# NEW_POT.net
KiCad netlist of a schematic drawn in EAGLE
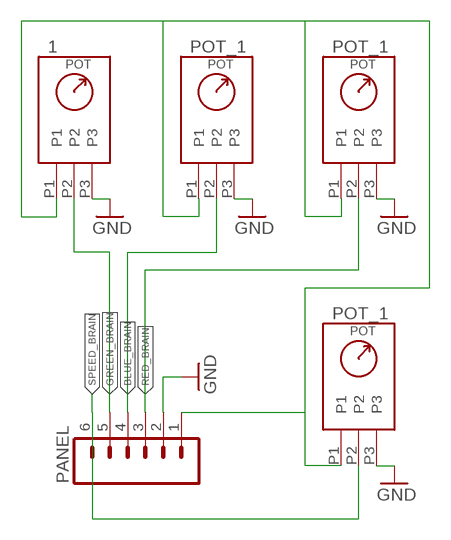
[diagram p0: schematic, sheet 1]

(export (version "E")
  (design (tool "Eeschema 10.0.6"))
  (components
    (comp (ref "DAS")
      (value "1")
      (footprint "eagle-import:POT_1")
      (libsource (lib "eagle-import") (part "POT_1"))
    )
    (comp (ref "PANEL")
      (value "M06NO_SILK_FEMALE_PTH")
      (footprint "eagle-import:1X06_NO_SILK")
      (libsource (lib "eagle-import") (part "M06NO_SILK_FEMALE_PTH"))
    )
    (comp (ref "U$2")
      (value "POT_1")
      (footprint "eagle-import:POT_1")
      (libsource (lib "eagle-import") (part "POT_1"))
    )
    (comp (ref "U$3")
      (value "POT_1")
      (footprint "eagle-import:POT_1")
      (libsource (lib "eagle-import") (part "POT_1"))
    )
    (comp (ref "U$4")
      (value "POT_1")
      (footprint "eagle-import:POT_1")
      (libsource (lib "eagle-import") (part "POT_1"))
    )
  )
  (nets
    (net (code "1") (name "BLUE_BRAIN") (class "Default")
      (node (ref "PANEL") (pin "4") (pinfunction "4_4") (pintype "passive"))
      (node (ref "U$2") (pin "P2") (pinfunction "P2_P2") (pintype "bidirectional"))
    )
    (net (code "2") (name "GND") (class "Default")
      (node (ref "DAS") (pin "P3") (pinfunction "P3_P3") (pintype "bidirectional"))
      (node (ref "PANEL") (pin "2") (pinfunction "2_2") (pintype "passive"))
      (node (ref "U$2") (pin "P3") (pinfunction "P3_P3") (pintype "bidirectional"))
      (node (ref "U$3") (pin "P3") (pinfunction "P3_P3") (pintype "bidirectional"))
      (node (ref "U$4") (pin "P3") (pinfunction "P3_P3") (pintype "bidirectional"))
    )
    (net (code "3") (name "GREEN_BRAIN") (class "Default")
      (node (ref "DAS") (pin "P2") (pinfunction "P2_P2") (pintype "bidirectional"))
      (node (ref "PANEL") (pin "5") (pinfunction "5_5") (pintype "passive"))
    )
    (net (code "4") (name "Net-(DAS-PadP1)") (class "Default")
      (node (ref "DAS") (pin "P1") (pinfunction "P1_P1") (pintype "bidirectional"))
      (node (ref "PANEL") (pin "1") (pinfunction "1_1") (pintype "passive"))
      (node (ref "U$2") (pin "P1") (pinfunction "P1_P1") (pintype "bidirectional"))
      (node (ref "U$3") (pin "P1") (pinfunction "P1_P1") (pintype "bidirectional"))
      (node (ref "U$4") (pin "P1") (pinfunction "P1_P1") (pintype "bidirectional"))
    )
    (net (code "5") (name "RED_BRAIN") (class "Default")
      (node (ref "PANEL") (pin "3") (pinfunction "3_3") (pintype "passive"))
      (node (ref "U$3") (pin "P2") (pinfunction "P2_P2") (pintype "bidirectional"))
    )
    (net (code "6") (name "SPEED_BRAIN") (class "Default")
      (node (ref "PANEL") (pin "6") (pinfunction "6_6") (pintype "passive"))
      (node (ref "U$4") (pin "P2") (pinfunction "P2_P2") (pintype "bidirectional"))
    )
  )
)
